# Velvet_Controller.net
KiCad netlist of a schematic drawn in Altium Designer
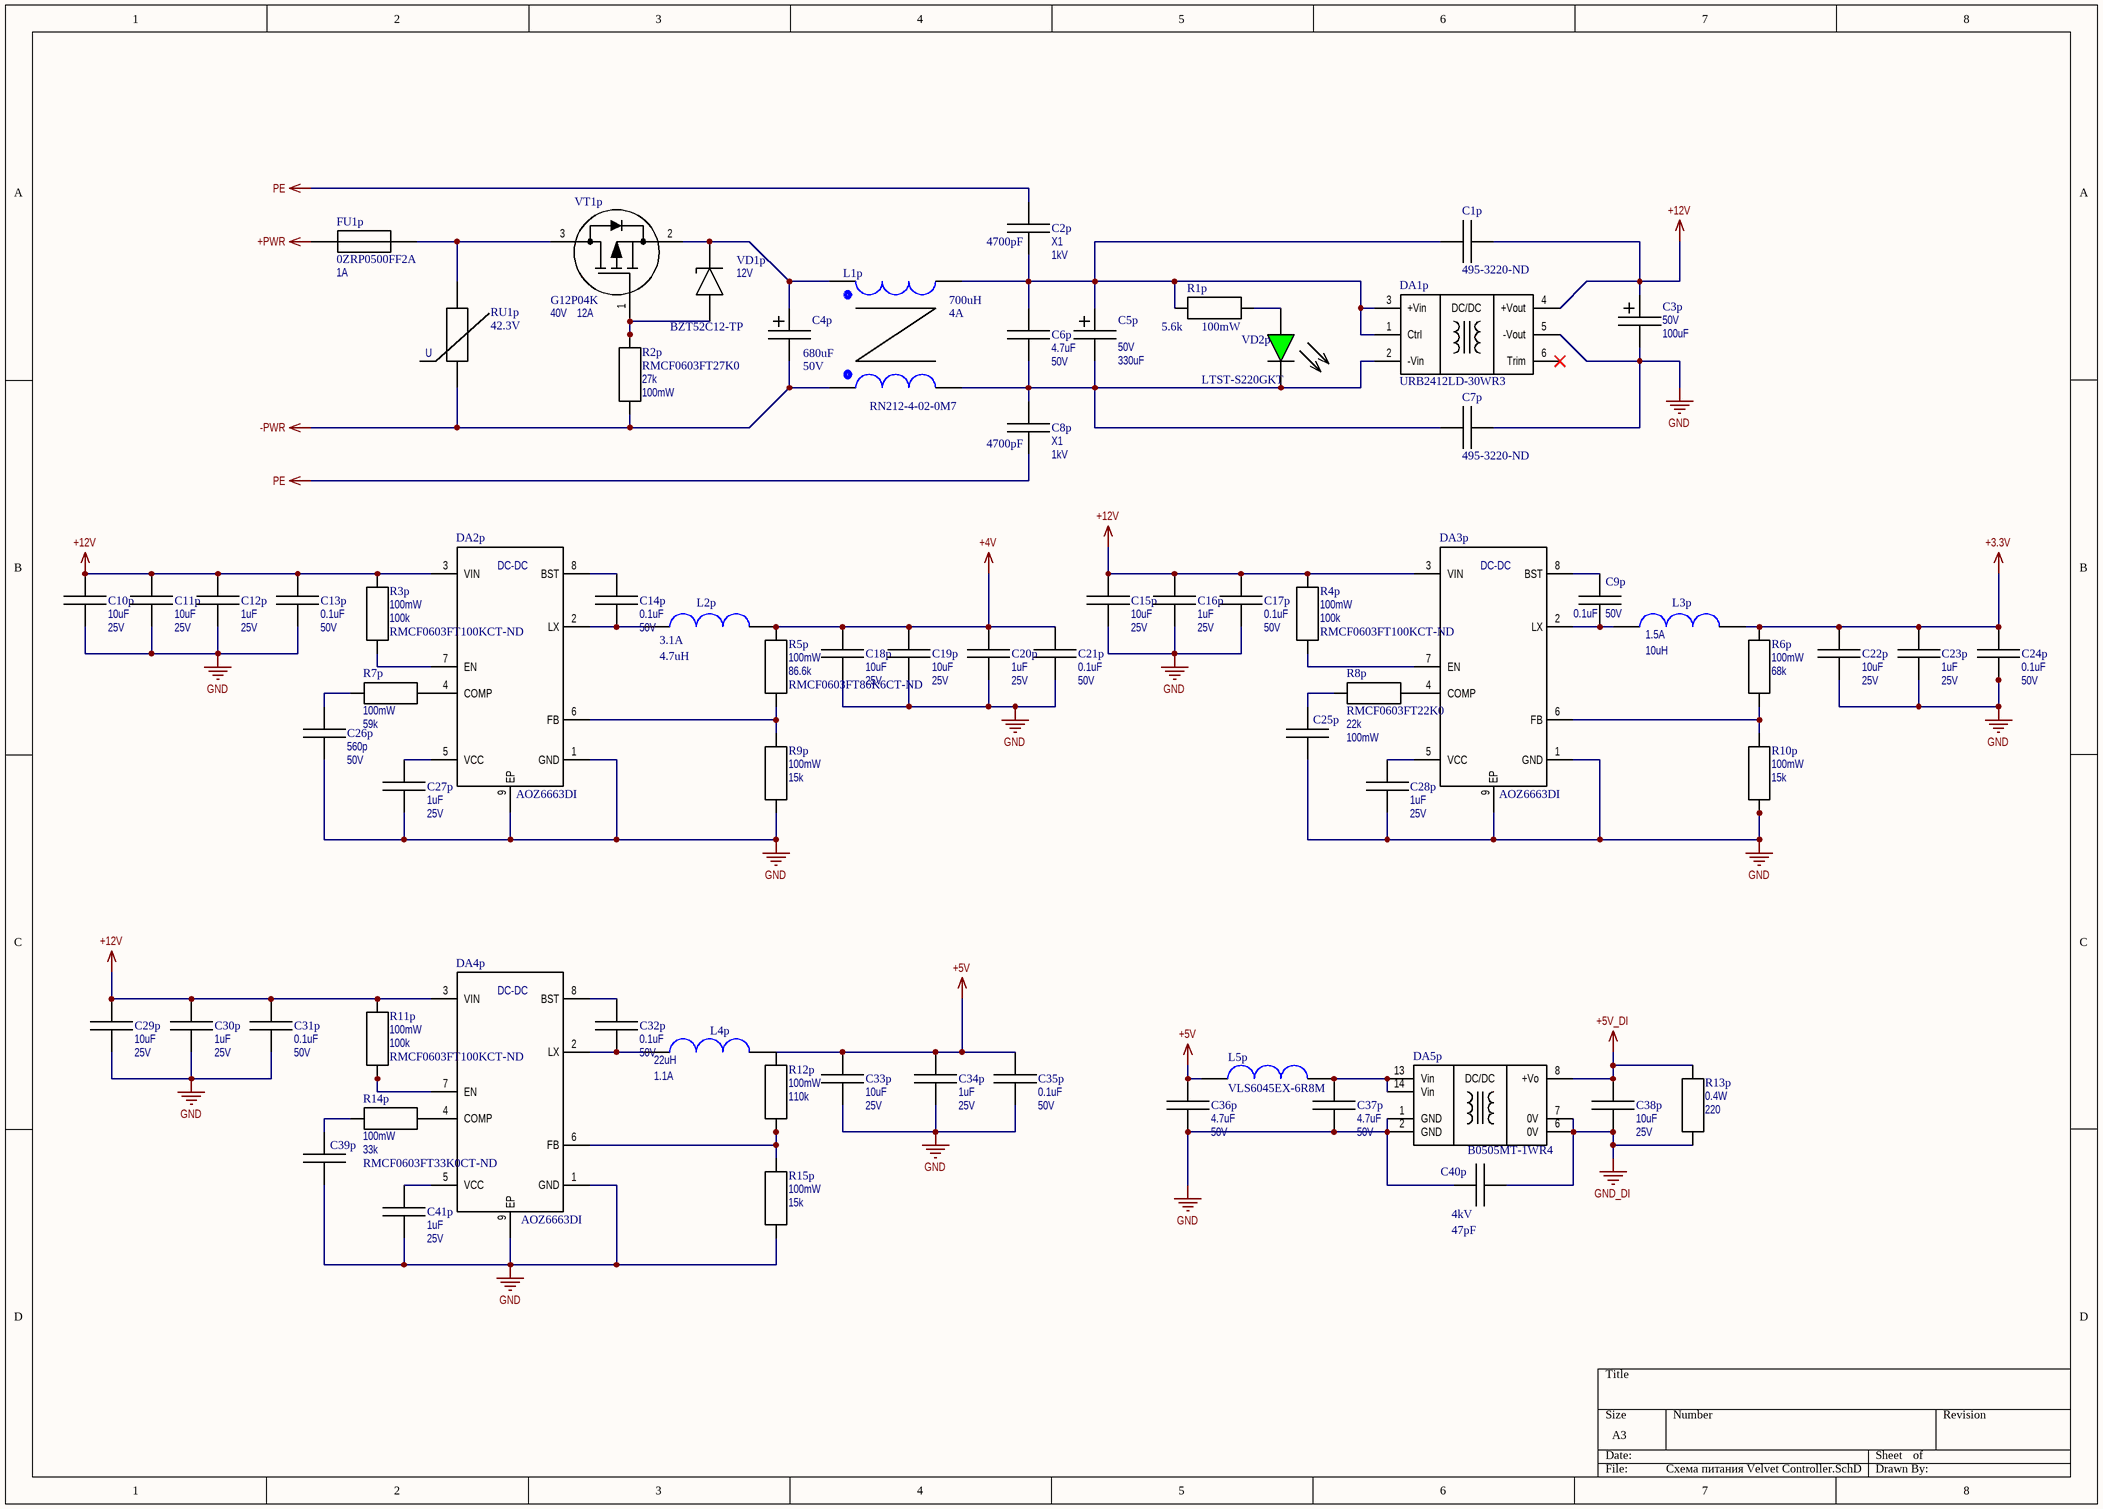
[diagram p0: Схема питания Velvet Controller.SchDoc]

(export (version "E")
  (design (tool "Eeschema 10.0.6"))
  (components
    (comp (ref "C1p")
      (value "B32672L8122J000")
      (footprint "CAP RADIAL L18.0 W5.0 H10.5 P15.0")
      (description "CAP FILM 1200PF 5% 2KVDC RADIAL")
      (fields (field (name "TOLERANCE") "5%") (field (name "SUPPLIER PART NUMBER 1") "495-3220-ND"))
      (libsource (lib "Passive components") (part "B32672L8122J000"))
    )
    (comp (ref "C2p")
      (value "R474F147050A1M")
      (footprint "CAP RADIAL L13.0 W4.0 H9.1 P10.0")
      (description "CAP FILM 4700PF 20% 1KVDC RAD")
      (fields
        (field (name "TOLERANCE") "20%")
        (field (name "CAPACITANCE") "4700pF")
        (field (name "TYPE") "X1")
        (field (name "RATED VOLTAGE") "1kV")
      )
      (libsource (lib "Passive components") (part "R474F147050A1M"))
    )
    (comp (ref "C3p")
      (value "ECA-1HM101B")
      (footprint "CAP RADIAL D8.0 L12.0 P5.0")
      (description "CAP ALUM 100UF 20% 50V RADIAL")
      (fields
        (field (name "TOLERANCE") "20%")
        (field (name "VOLTAGE RATED") "50V")
        (field (name "CAPACITANCE") "100uF")
      )
      (libsource (lib "Passive components") (part "ECA-1HM101B"))
    )
    (comp (ref "C4p")
      (value "50PX680MEFC12.5X20")
      (footprint "CAP RADIAL D12.5 L20.0 P5.0")
      (description "CAP ALUM 680UF 20% 50V RADIAL")
      (fields
        (field (name "CAPACITANCE") "680uF")
        (field (name "VOLTAGE RATED") "50V")
        (field (name "TOLERANCE") "20%")
      )
      (libsource (lib "Passive components") (part "50PX680MEFC12.5X20"))
    )
    (comp (ref "C5p")
      (value "ECA-1HM331B")
      (footprint "CAP RADIAL D10.0 L17,0 P5.0")
      (description "CAP ALUM 330UF 20% 50V RADIAL")
      (fields
        (field (name "TOLERANCE") "20%")
        (field (name "VOLTAGE RATED") "50V")
        (field (name "CAPACITANCE") "330uF")
      )
      (libsource (lib "Passive components") (part "ECA-1HM331B"))
    )
    (comp (ref "C6p")
      (value "CL21A475KBQNNNE")
      (footprint "CAP 0805 IPC MAX")
      (description "CAP SMD CER 4.7UF 50V X5R 0805")
      (fields
        (field (name "TOLERANCE") "10%")
        (field (name "CAPACITANCE") "4.7uF")
        (field (name "RATED VOLTAGE") "50V")
      )
      (libsource (lib "Passive components") (part "CL21A475KBQNNNE"))
    )
    (comp (ref "C7p")
      (value "B32672L8122J000")
      (footprint "CAP RADIAL L18.0 W5.0 H10.5 P15.0")
      (description "CAP FILM 1200PF 5% 2KVDC RADIAL")
      (fields (field (name "TOLERANCE") "5%") (field (name "SUPPLIER PART NUMBER 1") "495-3220-ND"))
      (libsource (lib "Passive components") (part "B32672L8122J000"))
    )
    (comp (ref "C8p")
      (value "R474F147050A1M")
      (footprint "CAP RADIAL L13.0 W4.0 H9.1 P10.0")
      (description "CAP FILM 4700PF 20% 1KVDC RAD")
      (fields
        (field (name "TOLERANCE") "20%")
        (field (name "CAPACITANCE") "4700pF")
        (field (name "TYPE") "X1")
        (field (name "RATED VOLTAGE") "1kV")
      )
      (libsource (lib "Passive components") (part "R474F147050A1M"))
    )
    (comp (ref "C9p")
      (value "GCM188R71H104KA57D")
      (footprint "CAP 0603 IPC MAX")
      (description "CAP SMD CER 0.1UF 50V X7R 0603")
      (fields
        (field (name "TOLERANCE") "10%")
        (field (name "CAPACITANCE") "0.1uF")
        (field (name "RATED VOLTAGE") "50V")
      )
      (libsource (lib "Passive components") (part "GCM188R71H104KA57D"))
    )
    (comp (ref "C10p")
      (value "CL31B106KAHNNNE")
      (footprint "CAP 1206 IPC MAX")
      (description "CAP SMD CER 10UF 25V X7R 1206")
      (fields
        (field (name "TOLERANCE") "10%")
        (field (name "CAPACITANCE") "10uF")
        (field (name "RATED VOLTAGE") "25V")
      )
      (libsource (lib "Passive components") (part "CL31B106KAHNNNE"))
    )
    (comp (ref "C11p")
      (value "CL31B106KAHNNNE")
      (footprint "CAP 1206 IPC MAX")
      (description "CAP SMD CER 10UF 25V X7R 1206")
      (fields
        (field (name "TOLERANCE") "10%")
        (field (name "CAPACITANCE") "10uF")
        (field (name "RATED VOLTAGE") "25V")
      )
      (libsource (lib "Passive components") (part "CL31B106KAHNNNE"))
    )
    (comp (ref "C12p")
      (value "TMK107BJ105KA-T")
      (footprint "CAP 0603 IPC MAX")
      (description "CAP SMD CER 1UF 25V X5R 0603")
      (fields
        (field (name "TOLERANCE") "10%")
        (field (name "CAPACITANCE") "1uF")
        (field (name "RATED VOLTAGE") "25V")
      )
      (libsource (lib "Passive components") (part "TMK107BJ105KA-T"))
    )
    (comp (ref "C13p")
      (value "GCM188R71H104KA57D")
      (footprint "CAP 0603 IPC MAX")
      (description "CAP SMD CER 0.1UF 50V X7R 0603")
      (fields
        (field (name "TOLERANCE") "10%")
        (field (name "CAPACITANCE") "0.1uF")
        (field (name "RATED VOLTAGE") "50V")
      )
      (libsource (lib "Passive components") (part "GCM188R71H104KA57D"))
    )
    (comp (ref "C14p")
      (value "GCM188R71H104KA57D")
      (footprint "CAP 0603 IPC MAX")
      (description "CAP SMD CER 0.1UF 50V X7R 0603")
      (fields
        (field (name "TOLERANCE") "10%")
        (field (name "CAPACITANCE") "0.1uF")
        (field (name "RATED VOLTAGE") "50V")
      )
      (libsource (lib "Passive components") (part "GCM188R71H104KA57D"))
    )
    (comp (ref "C15p")
      (value "CL31B106KAHNNNE")
      (footprint "CAP 1206 IPC MAX")
      (description "CAP SMD CER 10UF 25V X7R 1206")
      (fields
        (field (name "TOLERANCE") "10%")
        (field (name "CAPACITANCE") "10uF")
        (field (name "RATED VOLTAGE") "25V")
      )
      (libsource (lib "Passive components") (part "CL31B106KAHNNNE"))
    )
    (comp (ref "C16p")
      (value "TMK107BJ105KA-T")
      (footprint "CAP 0603 IPC MAX")
      (description "CAP SMD CER 1UF 25V X5R 0603")
      (fields
        (field (name "TOLERANCE") "10%")
        (field (name "CAPACITANCE") "1uF")
        (field (name "RATED VOLTAGE") "25V")
      )
      (libsource (lib "Passive components") (part "TMK107BJ105KA-T"))
    )
    (comp (ref "C17p")
      (value "GCM188R71H104KA57D")
      (footprint "CAP 0603 IPC MAX")
      (description "CAP SMD CER 0.1UF 50V X7R 0603")
      (fields
        (field (name "TOLERANCE") "10%")
        (field (name "CAPACITANCE") "0.1uF")
        (field (name "RATED VOLTAGE") "50V")
      )
      (libsource (lib "Passive components") (part "GCM188R71H104KA57D"))
    )
    (comp (ref "C18p")
      (value "CL31B106KAHNNNE")
      (footprint "CAP 1206 IPC MAX")
      (description "CAP SMD CER 10UF 25V X7R 1206")
      (fields
        (field (name "TOLERANCE") "10%")
        (field (name "CAPACITANCE") "10uF")
        (field (name "RATED VOLTAGE") "25V")
      )
      (libsource (lib "Passive components") (part "CL31B106KAHNNNE"))
    )
    (comp (ref "C19p")
      (value "CL31B106KAHNNNE")
      (footprint "CAP 1206 IPC MAX")
      (description "CAP SMD CER 10UF 25V X7R 1206")
      (fields
        (field (name "TOLERANCE") "10%")
        (field (name "CAPACITANCE") "10uF")
        (field (name "RATED VOLTAGE") "25V")
      )
      (libsource (lib "Passive components") (part "CL31B106KAHNNNE"))
    )
    (comp (ref "C20p")
      (value "TMK107BJ105KA-T")
      (footprint "CAP 0603 IPC MAX")
      (description "CAP SMD CER 1UF 25V X5R 0603")
      (fields
        (field (name "TOLERANCE") "10%")
        (field (name "CAPACITANCE") "1uF")
        (field (name "RATED VOLTAGE") "25V")
      )
      (libsource (lib "Passive components") (part "TMK107BJ105KA-T"))
    )
    (comp (ref "C21p")
      (value "GCM188R71H104KA57D")
      (footprint "CAP 0603 IPC MAX")
      (description "CAP SMD CER 0.1UF 50V X7R 0603")
      (fields
        (field (name "TOLERANCE") "10%")
        (field (name "CAPACITANCE") "0.1uF")
        (field (name "RATED VOLTAGE") "50V")
      )
      (libsource (lib "Passive components") (part "GCM188R71H104KA57D"))
    )
    (comp (ref "C22p")
      (value "CL31B106KAHNNNE")
      (footprint "CAP 1206 IPC MAX")
      (description "CAP SMD CER 10UF 25V X7R 1206")
      (fields
        (field (name "TOLERANCE") "10%")
        (field (name "CAPACITANCE") "10uF")
        (field (name "RATED VOLTAGE") "25V")
      )
      (libsource (lib "Passive components") (part "CL31B106KAHNNNE"))
    )
    (comp (ref "C23p")
      (value "TMK107BJ105KA-T")
      (footprint "CAP 0603 IPC MAX")
      (description "CAP SMD CER 1UF 25V X5R 0603")
      (fields
        (field (name "TOLERANCE") "10%")
        (field (name "CAPACITANCE") "1uF")
        (field (name "RATED VOLTAGE") "25V")
      )
      (libsource (lib "Passive components") (part "TMK107BJ105KA-T"))
    )
    (comp (ref "C24p")
      (value "GCM188R71H104KA57D")
      (footprint "CAP 0603 IPC MAX")
      (description "CAP SMD CER 0.1UF 50V X7R 0603")
      (fields
        (field (name "TOLERANCE") "10%")
        (field (name "CAPACITANCE") "0.1uF")
        (field (name "RATED VOLTAGE") "50V")
      )
      (libsource (lib "Passive components") (part "GCM188R71H104KA57D"))
    )
    (comp (ref "C25p")
      (value "CAP")
      (footprint "RES 0603 IPC MAX")
      (description "CAP ??UF ??% ??V Package?")
      (libsource (lib "Passive components") (part "CAP GOST"))
    )
    (comp (ref "C26p")
      (value "CC0603KRX7R9BB561")
      (footprint "CAP 0603 IPC MAX")
      (description "CAP SMD CER 560PF 50V X7R 0603")
      (fields
        (field (name "TOLERANCE") "10%")
        (field (name "CAPACITANCE") "560p")
        (field (name "RATED VOLTAGE") "50V")
      )
      (libsource (lib "Passive components") (part "CC0603KRX7R9BB561"))
    )
    (comp (ref "C27p")
      (value "TMK107BJ105KA-T")
      (footprint "CAP 0603 IPC MAX")
      (description "CAP SMD CER 1UF 25V X5R 0603")
      (fields
        (field (name "TOLERANCE") "10%")
        (field (name "CAPACITANCE") "1uF")
        (field (name "RATED VOLTAGE") "25V")
      )
      (libsource (lib "Passive components") (part "TMK107BJ105KA-T"))
    )
    (comp (ref "C28p")
      (value "TMK107BJ105KA-T")
      (footprint "CAP 0603 IPC MAX")
      (description "CAP SMD CER 1UF 25V X5R 0603")
      (fields
        (field (name "TOLERANCE") "10%")
        (field (name "CAPACITANCE") "1uF")
        (field (name "RATED VOLTAGE") "25V")
      )
      (libsource (lib "Passive components") (part "TMK107BJ105KA-T"))
    )
    (comp (ref "C29p")
      (value "CL31B106KAHNNNE")
      (footprint "CAP 1206 IPC MAX")
      (description "CAP SMD CER 10UF 25V X7R 1206")
      (fields
        (field (name "TOLERANCE") "10%")
        (field (name "CAPACITANCE") "10uF")
        (field (name "RATED VOLTAGE") "25V")
      )
      (libsource (lib "Passive components") (part "CL31B106KAHNNNE"))
    )
    (comp (ref "C30p")
      (value "TMK107BJ105KA-T")
      (footprint "CAP 0603 IPC MAX")
      (description "CAP SMD CER 1UF 25V X5R 0603")
      (fields
        (field (name "TOLERANCE") "10%")
        (field (name "CAPACITANCE") "1uF")
        (field (name "RATED VOLTAGE") "25V")
      )
      (libsource (lib "Passive components") (part "TMK107BJ105KA-T"))
    )
    (comp (ref "C31p")
      (value "GCM188R71H104KA57D")
      (footprint "CAP 0603 IPC MAX")
      (description "CAP SMD CER 0.1UF 50V X7R 0603")
      (fields
        (field (name "TOLERANCE") "10%")
        (field (name "CAPACITANCE") "0.1uF")
        (field (name "RATED VOLTAGE") "50V")
      )
      (libsource (lib "Passive components") (part "GCM188R71H104KA57D"))
    )
    (comp (ref "C32p")
      (value "GCM188R71H104KA57D")
      (footprint "CAP 0603 IPC MAX")
      (description "CAP SMD CER 0.1UF 50V X7R 0603")
      (fields
        (field (name "TOLERANCE") "10%")
        (field (name "CAPACITANCE") "0.1uF")
        (field (name "RATED VOLTAGE") "50V")
      )
      (libsource (lib "Passive components") (part "GCM188R71H104KA57D"))
    )
    (comp (ref "C33p")
      (value "CL31B106KAHNNNE")
      (footprint "CAP 1206 IPC MAX")
      (description "CAP SMD CER 10UF 25V X7R 1206")
      (fields
        (field (name "TOLERANCE") "10%")
        (field (name "CAPACITANCE") "10uF")
        (field (name "RATED VOLTAGE") "25V")
      )
      (libsource (lib "Passive components") (part "CL31B106KAHNNNE"))
    )
    (comp (ref "C34p")
      (value "TMK107BJ105KA-T")
      (footprint "CAP 0603 IPC MAX")
      (description "CAP SMD CER 1UF 25V X5R 0603")
      (fields
        (field (name "TOLERANCE") "10%")
        (field (name "CAPACITANCE") "1uF")
        (field (name "RATED VOLTAGE") "25V")
      )
      (libsource (lib "Passive components") (part "TMK107BJ105KA-T"))
    )
    (comp (ref "C35p")
      (value "GCM188R71H104KA57D")
      (footprint "CAP 0603 IPC MAX")
      (description "CAP SMD CER 0.1UF 50V X7R 0603")
      (fields
        (field (name "TOLERANCE") "10%")
        (field (name "CAPACITANCE") "0.1uF")
        (field (name "RATED VOLTAGE") "50V")
      )
      (libsource (lib "Passive components") (part "GCM188R71H104KA57D"))
    )
    (comp (ref "C36p")
      (value "CL21A475KBQNNNE")
      (footprint "CAP 0805 IPC MAX")
      (description "CAP SMD CER 4.7UF 50V X5R 0805")
      (fields
        (field (name "TOLERANCE") "10%")
        (field (name "CAPACITANCE") "4.7uF")
        (field (name "RATED VOLTAGE") "50V")
      )
      (libsource (lib "Passive components") (part "CL21A475KBQNNNE"))
    )
    (comp (ref "C37p")
      (value "CL21A475KBQNNNE")
      (footprint "CAP 0805 IPC MAX")
      (description "CAP SMD CER 4.7UF 50V X5R 0805")
      (fields
        (field (name "TOLERANCE") "10%")
        (field (name "CAPACITANCE") "4.7uF")
        (field (name "RATED VOLTAGE") "50V")
      )
      (libsource (lib "Passive components") (part "CL21A475KBQNNNE"))
    )
    (comp (ref "C38p")
      (value "CL31B106KAHNNNE")
      (footprint "CAP 1206 IPC MAX")
      (description "CAP SMD CER 10UF 25V X7R 1206")
      (fields
        (field (name "TOLERANCE") "10%")
        (field (name "CAPACITANCE") "10uF")
        (field (name "RATED VOLTAGE") "25V")
      )
      (libsource (lib "Passive components") (part "CL31B106KAHNNNE"))
    )
    (comp (ref "C39p")
      (value "CAP")
      (footprint "RES 0603 IPC MAX")
      (description "CAP ??UF ??% ??V Package?")
      (libsource (lib "Passive components") (part "CAP GOST"))
    )
    (comp (ref "C40p")
      (value "CC45SL3JD470JYVNA")
      (footprint "CC45SL3JD470JYVNA")
      (description "CAP SMD CER 47PF 6KV SL RADIAL")
      (fields
        (field (name "CAPACITANCE") "47pF")
        (field (name "TOLERANCE") "5%")
        (field (name "RATED VOLTAGE") "4kV")
      )
      (libsource (lib "Passive components") (part "CC45SL3JD470JYVNA"))
    )
    (comp (ref "C41p")
      (value "TMK107BJ105KA-T")
      (footprint "CAP 0603 IPC MAX")
      (description "CAP SMD CER 1UF 25V X5R 0603")
      (fields
        (field (name "TOLERANCE") "10%")
        (field (name "CAPACITANCE") "1uF")
        (field (name "RATED VOLTAGE") "25V")
      )
      (libsource (lib "Passive components") (part "TMK107BJ105KA-T"))
    )
    (comp (ref "DA1p")
      (value "URB2412LD-30WR3")
      (footprint "URB2412LD-30WR3")
      (description "DC DC CONVERTER 12V 30W")
      (libsource (lib "Power") (part "URB2412LD-30WR3"))
    )
    (comp (ref "DA2p")
      (value "AOZ6663DI")
      (footprint "DFN 3x3-8L")
      (description "IC REG BUCK ADJ 3A 8DFN")
      (libsource (lib "Power") (part "AOZ6663DI"))
    )
    (comp (ref "DA3p")
      (value "AOZ6663DI")
      (footprint "DFN 3x3-8L")
      (description "IC REG BUCK ADJ 3A 8DFN")
      (libsource (lib "Power") (part "AOZ6663DI"))
    )
    (comp (ref "DA4p")
      (value "AOZ6663DI")
      (footprint "DFN 3x3-8L")
      (description "IC REG BUCK ADJ 3A 8DFN")
      (libsource (lib "Power") (part "AOZ6663DI"))
    )
    (comp (ref "DA5p")
      (value "B0505MT-1WR4")
      (footprint "B0505MT-1WR4")
      (description "DC DC CONVERTER 5V 1W")
      (libsource (lib "Power") (part "B0505MT-1WR4"))
    )
    (comp (ref "FU1p")
      (value "0ZRP0500FF2A")
      (footprint "0ZRP0500FF2A")
      (description "PTC RESET FUSE 60V 5A RADIAL")
      (fields (field (name "CURRENT HOLD") "1A"))
      (libsource (lib "Power") (part "0ZRP0500FF2A"))
    )
    (comp (ref "L1p")
      (value "RN212-4-02-0M7")
      (footprint "FIXED IND RN212-4-02-0M7")
      (description "COMMON MODE CHOKE 700UH 4A 2LN TH")
      (fields (field (name "INDUCTANCE") "700uH") (field (name "CURRENT RATING") "4A"))
      (libsource (lib "Passive components") (part "RN212-4-02-0M7"))
    )
    (comp (ref "L2p")
      (value "SRN5040-4R7M")
      (footprint "SRN5040")
      (description "FIXED IND 4.7UH 3.1A 35 MOHM SMD")
      (fields (field (name "INDUCTANCE") "4.7uH") (field (name "CURRENT RATING") "3.1A"))
      (libsource (lib "Passive components") (part "SRN5040-4R7M"))
    )
    (comp (ref "L3p")
      (value "ASPI-4030S-100M-T")
      (footprint "ASPI-4030S")
      (description "FIXED IND 10UH 1.5A 100 MOHM SMD")
      (fields (field (name "INDUCTANCE") "10uH") (field (name "CURRENT RATING") "1.5A"))
      (libsource (lib "Passive components") (part "ASPI-4030S-100M-T"))
    )
    (comp (ref "L4p")
      (value "TYS5020220M-10")
      (footprint "TYS5020")
      (description "FIXED IND 22UH 1.1A 226 MOHM SMD")
      (fields (field (name "INDUCTANCE") "22uH") (field (name "CURRENT RATING") "1.1A"))
      (libsource (lib "Passive components") (part "TYS5020220M-10"))
    )
    (comp (ref "L5p")
      (value "VLS6045EX-6R8M")
      (footprint "VLS6045EX")
      (description "FIXED IND 6.8UH 3.6A 36 MOHM SMD")
      (libsource (lib "Passive components") (part "VLS6045EX-6R8M"))
    )
    (comp (ref "R1p")
      (value "RMCF0603FT5K60")
      (footprint "RES 0603 IPC MAX")
      (description "RES SMD 5.6K OHM 1% 1/10W 0603")
      (fields
        (field (name "RESISTANCE") "5.6k")
        (field (name "TOLERANCE") "1%")
        (field (name "RATED POWER") "100mW")
      )
      (libsource (lib "Passive components") (part "RMCF0603FT5K60"))
    )
    (comp (ref "R2p")
      (value "RMCF0603FT27K0")
      (footprint "RES 0603 IPC MAX")
      (description "RES SMD 27K OHM 1% 1/10W 0603")
      (fields
        (field (name "TOLERANCE") "1%")
        (field (name "RESISTANCE") "27k")
        (field (name "RATED POWER") "100mW")
      )
      (libsource (lib "Passive components") (part "RMCF0603FT27K0"))
    )
    (comp (ref "R3p")
      (value "RMCF0603FT100K")
      (footprint "RES 0603 IPC MAX")
      (description "RES SMD 100K OHM 5% 1/10W 0603")
      (fields
        (field (name "TOLERANCE") "5%")
        (field (name "POWER RATED") "100mW")
        (field (name "RESISTANCE") "100k")
        (field (name "SUPPLIER PART NUMBER 1") "RMCF0603FT100KCT-ND")
      )
      (libsource (lib "Passive components") (part "RMCF0603FT100K"))
    )
    (comp (ref "R4p")
      (value "RMCF0603FT100K")
      (footprint "RES 0603 IPC MAX")
      (description "RES SMD 100K OHM 5% 1/10W 0603")
      (fields
        (field (name "TOLERANCE") "5%")
        (field (name "POWER RATED") "100mW")
        (field (name "RESISTANCE") "100k")
        (field (name "SUPPLIER PART NUMBER 1") "RMCF0603FT100KCT-ND")
      )
      (libsource (lib "Passive components") (part "RMCF0603FT100K"))
    )
    (comp (ref "R5p")
      (value "RMCF0603FT86K6")
      (footprint "RES 0603 IPC MAX")
      (description "RES SMD 86.6K OHM 5% 1/10W 0603")
      (fields
        (field (name "TOLERANCE") "5%")
        (field (name "POWER RATED") "100mW")
        (field (name "RESISTANCE") "86.6k")
        (field (name "SUPPLIER PART NUMBER 1") "RMCF0603FT86K6CT-ND")
      )
      (libsource (lib "Passive components") (part "RMCF0603FT86K6"))
    )
    (comp (ref "R6p")
      (value "RMCF0603FT68K0")
      (footprint "RES 0603 IPC MAX")
      (description "RES SMD 68K OHM 1% 1/10W 0603")
      (fields
        (field (name "TOLERANCE") "1%")
        (field (name "POWER RATED") "100mW")
        (field (name "RESISTANCE") "68k")
      )
      (libsource (lib "Passive components") (part "RMCF0603FT68K0"))
    )
    (comp (ref "R7p")
      (value "RMCF0603FT59K0")
      (footprint "RES 0603 IPC MAX")
      (description "RES SMD 59K OHM 5% 1/10W 0603")
      (fields
        (field (name "TOLERANCE") "5%")
        (field (name "POWER RATED") "100mW")
        (field (name "RESISTANCE") "59k")
      )
      (libsource (lib "Passive components") (part "RMCF0603FT59K0"))
    )
    (comp (ref "R8p")
      (value "RMCF0603FT22K0")
      (footprint "RES 0603 IPC MAX")
      (description "RES SMD 22K OHM 1% 1/10W 0603")
      (fields
        (field (name "TOLERANCE") "1%")
        (field (name "RESISTANCE") "22k")
        (field (name "POWER RATED") "100mW")
      )
      (libsource (lib "Passive components") (part "RMCF0603FT22K0"))
    )
    (comp (ref "R9p")
      (value "RMCF0603FT15K0")
      (footprint "RES 0603 IPC MAX")
      (description "RES SMD 15K OHM 1% 1/10W 0603")
      (fields
        (field (name "TOLERANCE") "1%")
        (field (name "POWER RATED") "100mW")
        (field (name "RESISTANCE") "15k")
      )
      (libsource (lib "Passive components") (part "RMCF0603FT15K0"))
    )
    (comp (ref "R10p")
      (value "RMCF0603FT15K0")
      (footprint "RES 0603 IPC MAX")
      (description "RES SMD 15K OHM 1% 1/10W 0603")
      (fields
        (field (name "TOLERANCE") "1%")
        (field (name "POWER RATED") "100mW")
        (field (name "RESISTANCE") "15k")
      )
      (libsource (lib "Passive components") (part "RMCF0603FT15K0"))
    )
    (comp (ref "R11p")
      (value "RMCF0603FT100K")
      (footprint "RES 0603 IPC MAX")
      (description "RES SMD 100K OHM 5% 1/10W 0603")
      (fields
        (field (name "TOLERANCE") "5%")
        (field (name "POWER RATED") "100mW")
        (field (name "RESISTANCE") "100k")
        (field (name "SUPPLIER PART NUMBER 1") "RMCF0603FT100KCT-ND")
      )
      (libsource (lib "Passive components") (part "RMCF0603FT100K"))
    )
    (comp (ref "R12p")
      (value "RMCF0603FT110K")
      (footprint "RES 0603 IPC MAX")
      (description "RES SMD 110K OHM 1% 1/10W 0603")
      (fields
        (field (name "TOLERANCE") "5%")
        (field (name "POWER RATED") "100mW")
        (field (name "RESISTANCE") "110k")
      )
      (libsource (lib "Passive components") (part "RMCF0603FT110K"))
    )
    (comp (ref "R13p")
      (value "ESR10EZPF2200")
      (footprint "RES 0805 IPC MAX")
      (description "RES SMD 220 OHM 1% 0.4W 0805")
      (fields
        (field (name "TOLERANCE") "1%")
        (field (name "POWER RATED") "0.4W")
        (field (name "RESISTANCE") "220")
      )
      (libsource (lib "Passive components") (part "ESR10EZPF2200"))
    )
    (comp (ref "R14p")
      (value "RMCF0603FT33K0")
      (footprint "RES 0603 IPC MAX")
      (description "RES SMD 33K OHM 1% 1/10W 0603")
      (fields
        (field (name "TOLERANCE") "1%")
        (field (name "POWER RATED") "100mW")
        (field (name "RESISTANCE") "33k")
        (field (name "SUPPLIER PART NUMBER 1") "RMCF0603FT33K0CT-ND")
      )
      (libsource (lib "Passive components") (part "RMCF0603FT33K0"))
    )
    (comp (ref "R15p")
      (value "RMCF0603FT15K0")
      (footprint "RES 0603 IPC MAX")
      (description "RES SMD 15K OHM 1% 1/10W 0603")
      (fields
        (field (name "TOLERANCE") "1%")
        (field (name "POWER RATED") "100mW")
        (field (name "RESISTANCE") "15k")
      )
      (libsource (lib "Passive components") (part "RMCF0603FT15K0"))
    )
    (comp (ref "RU1p")
      (value "B72220S0300K101")
      (footprint "B72220S0300K101")
      (description "VARISTOR 47V 2KA DISC 20MM S20K30")
      (fields (field (name "MANUFACTURER") "EPCOS Inc") (field (name "VARISTOR VOLTAGE (MIN)") "42.3V"))
      (libsource (lib "Power") (part "B72220S0300K101"))
    )
    (comp (ref "VD1p")
      (value "BZT52C12-TP")
      (footprint "SOD-123 (Marked)")
      (description "DIODE ZENER 12V 200MW SOD123")
      (fields (field (name "TOLERANCE") "5%") (field (name "ZENER VOLTAGE") "12V"))
      (libsource (lib "Diodes") (part "BZT52C12-TP"))
    )
    (comp (ref "VD2p")
      (value "LTST-S220GKT")
      (footprint "0805 DIODE")
      (description "LED GREEN CLEAR SMD R/A")
      (libsource (lib "Diodes") (part "LTST-S220GKT"))
    )
    (comp (ref "VT1p")
      (value "G12P04K")
      (footprint "TO-252 (D-PAK)")
      (description "MOSFET P-CH 40V 12A TO-252")
      (fields (field (name "VDS MAX") "40V") (field (name "MAX DRAIN CURRENT") "12A"))
      (libsource (lib "MOSFET") (part "G12P04K"))
    )
  )
  (nets
    (net (code "1") (name "+3.3V") (class "Default")
      (node (ref "C22p") (pin "1") (pinfunction "1_1") (pintype "passive"))
      (node (ref "C23p") (pin "1") (pinfunction "1_1") (pintype "passive"))
      (node (ref "C24p") (pin "1") (pinfunction "1_1") (pintype "passive"))
      (node (ref "L3p") (pin "2") (pinfunction "2_2") (pintype "passive"))
      (node (ref "R6p") (pin "1") (pinfunction "1_1") (pintype "passive"))
    )
    (net (code "2") (name "+4V") (class "Default")
      (node (ref "C18p") (pin "1") (pinfunction "1_1") (pintype "passive"))
      (node (ref "C19p") (pin "1") (pinfunction "1_1") (pintype "passive"))
      (node (ref "C20p") (pin "1") (pinfunction "1_1") (pintype "passive"))
      (node (ref "C21p") (pin "1") (pinfunction "1_1") (pintype "passive"))
      (node (ref "L2p") (pin "2") (pinfunction "2_2") (pintype "passive"))
      (node (ref "R5p") (pin "1") (pinfunction "1_1") (pintype "passive"))
    )
    (net (code "3") (name "+5V") (class "Default")
      (node (ref "C33p") (pin "1") (pinfunction "1_1") (pintype "passive"))
      (node (ref "C34p") (pin "1") (pinfunction "1_1") (pintype "passive"))
      (node (ref "C35p") (pin "1") (pinfunction "1_1") (pintype "passive"))
      (node (ref "C36p") (pin "1") (pinfunction "1_1") (pintype "passive"))
      (node (ref "L4p") (pin "2") (pinfunction "2_2") (pintype "passive"))
      (node (ref "L5p") (pin "1") (pinfunction "1_1") (pintype "passive"))
      (node (ref "R12p") (pin "2") (pinfunction "2_2") (pintype "passive"))
    )
    (net (code "4") (name "+5V_DI") (class "Default")
      (node (ref "C38p") (pin "1") (pinfunction "1_1") (pintype "passive"))
      (node (ref "DA5p") (pin "8") (pinfunction "+Vo_8") (pintype "passive"))
      (node (ref "R13p") (pin "2") (pinfunction "2_2") (pintype "passive"))
    )
    (net (code "5") (name "+12V") (class "Default")
      (node (ref "C10p") (pin "1") (pinfunction "1_1") (pintype "passive"))
      (node (ref "C11p") (pin "1") (pinfunction "1_1") (pintype "passive"))
      (node (ref "C12p") (pin "1") (pinfunction "1_1") (pintype "passive"))
      (node (ref "C13p") (pin "1") (pinfunction "1_1") (pintype "passive"))
      (node (ref "C15p") (pin "1") (pinfunction "1_1") (pintype "passive"))
      (node (ref "C16p") (pin "1") (pinfunction "1_1") (pintype "passive"))
      (node (ref "C17p") (pin "1") (pinfunction "1_1") (pintype "passive"))
      (node (ref "C1p") (pin "2") (pinfunction "2_2") (pintype "passive"))
      (node (ref "C29p") (pin "1") (pinfunction "1_1") (pintype "passive"))
      (node (ref "C30p") (pin "1") (pinfunction "1_1") (pintype "passive"))
      (node (ref "C31p") (pin "1") (pinfunction "1_1") (pintype "passive"))
      (node (ref "C3p") (pin "1") (pinfunction "1_1") (pintype "passive"))
      (node (ref "DA1p") (pin "4") (pinfunction "+Vout_4") (pintype "passive"))
      (node (ref "DA2p") (pin "3") (pinfunction "VIN_3") (pintype "passive"))
      (node (ref "DA3p") (pin "3") (pinfunction "VIN_3") (pintype "passive"))
      (node (ref "DA4p") (pin "3") (pinfunction "VIN_3") (pintype "passive"))
      (node (ref "R11p") (pin "1") (pinfunction "1_1") (pintype "passive"))
      (node (ref "R3p") (pin "2") (pinfunction "2_2") (pintype "passive"))
      (node (ref "R4p") (pin "1") (pinfunction "1_1") (pintype "passive"))
    )
    (net (code "6") (name "+PWR") (class "Default")
      (node (ref "FU1p") (pin "1") (pinfunction "1_1") (pintype "passive"))
    )
    (net (code "7") (name "-PWR") (class "Default")
      (node (ref "C4p") (pin "2") (pinfunction "2_2") (pintype "passive"))
      (node (ref "L1p") (pin "3") (pinfunction "3_3") (pintype "passive"))
      (node (ref "R2p") (pin "1") (pinfunction "1_1") (pintype "passive"))
      (node (ref "RU1p") (pin "1") (pinfunction "1_1") (pintype "passive"))
    )
    (net (code "8") (name "GND") (class "Default")
      (node (ref "C10p") (pin "2") (pinfunction "2_2") (pintype "passive"))
      (node (ref "C11p") (pin "2") (pinfunction "2_2") (pintype "passive"))
      (node (ref "C12p") (pin "2") (pinfunction "2_2") (pintype "passive"))
      (node (ref "C13p") (pin "2") (pinfunction "2_2") (pintype "passive"))
      (node (ref "C15p") (pin "2") (pinfunction "2_2") (pintype "passive"))
      (node (ref "C16p") (pin "2") (pinfunction "2_2") (pintype "passive"))
      (node (ref "C17p") (pin "2") (pinfunction "2_2") (pintype "passive"))
      (node (ref "C18p") (pin "2") (pinfunction "2_2") (pintype "passive"))
      (node (ref "C19p") (pin "2") (pinfunction "2_2") (pintype "passive"))
      (node (ref "C20p") (pin "2") (pinfunction "2_2") (pintype "passive"))
      (node (ref "C21p") (pin "2") (pinfunction "2_2") (pintype "passive"))
      (node (ref "C22p") (pin "2") (pinfunction "2_2") (pintype "passive"))
      (node (ref "C23p") (pin "2") (pinfunction "2_2") (pintype "passive"))
      (node (ref "C24p") (pin "2") (pinfunction "2_2") (pintype "passive"))
      (node (ref "C25p") (pin "2") (pinfunction "2_2") (pintype "passive"))
      (node (ref "C26p") (pin "2") (pinfunction "2_2") (pintype "passive"))
      (node (ref "C27p") (pin "2") (pinfunction "2_2") (pintype "passive"))
      (node (ref "C28p") (pin "2") (pinfunction "2_2") (pintype "passive"))
      (node (ref "C29p") (pin "2") (pinfunction "2_2") (pintype "passive"))
      (node (ref "C30p") (pin "2") (pinfunction "2_2") (pintype "passive"))
      (node (ref "C31p") (pin "2") (pinfunction "2_2") (pintype "passive"))
      (node (ref "C33p") (pin "2") (pinfunction "2_2") (pintype "passive"))
      (node (ref "C34p") (pin "2") (pinfunction "2_2") (pintype "passive"))
      (node (ref "C35p") (pin "2") (pinfunction "2_2") (pintype "passive"))
      (node (ref "C36p") (pin "2") (pinfunction "2_2") (pintype "passive"))
      (node (ref "C37p") (pin "2") (pinfunction "2_2") (pintype "passive"))
      (node (ref "C39p") (pin "2") (pinfunction "2_2") (pintype "passive"))
      (node (ref "C3p") (pin "2") (pinfunction "2_2") (pintype "passive"))
      (node (ref "C40p") (pin "1") (pinfunction "1_1") (pintype "passive"))
      (node (ref "C41p") (pin "2") (pinfunction "2_2") (pintype "passive"))
      (node (ref "C7p") (pin "2") (pinfunction "2_2") (pintype "passive"))
      (node (ref "DA1p") (pin "5") (pinfunction "-Vout_5") (pintype "passive"))
      (node (ref "DA2p") (pin "1") (pinfunction "GND_1") (pintype "passive"))
      (node (ref "DA2p") (pin "9") (pinfunction "EP_9") (pintype "passive"))
      (node (ref "DA3p") (pin "1") (pinfunction "GND_1") (pintype "passive"))
      (node (ref "DA3p") (pin "9") (pinfunction "EP_9") (pintype "passive"))
      (node (ref "DA4p") (pin "1") (pinfunction "GND_1") (pintype "passive"))
      (node (ref "DA4p") (pin "9") (pinfunction "EP_9") (pintype "passive"))
      (node (ref "DA5p") (pin "1") (pinfunction "GND_1") (pintype "passive"))
      (node (ref "DA5p") (pin "2") (pinfunction "GND_2") (pintype "passive"))
      (node (ref "R10p") (pin "1") (pinfunction "1_1") (pintype "passive"))
      (node (ref "R15p") (pin "1") (pinfunction "1_1") (pintype "passive"))
      (node (ref "R9p") (pin "1") (pinfunction "1_1") (pintype "passive"))
    )
    (net (code "9") (name "GND_DI") (class "Default")
      (node (ref "C38p") (pin "2") (pinfunction "2_2") (pintype "passive"))
      (node (ref "C40p") (pin "2") (pinfunction "2_2") (pintype "passive"))
      (node (ref "DA5p") (pin "6") (pinfunction "0V_6") (pintype "passive"))
      (node (ref "DA5p") (pin "7") (pinfunction "0V_7") (pintype "passive"))
      (node (ref "R13p") (pin "1") (pinfunction "1_1") (pintype "passive"))
    )
    (net (code "10") (name "Net-(C25p-Pad1)") (class "Default")
      (node (ref "C25p") (pin "1") (pinfunction "1_1") (pintype "passive"))
      (node (ref "R8p") (pin "1") (pinfunction "1_1") (pintype "passive"))
    )
    (net (code "11") (name "Net-(C26p-Pad1)") (class "Default")
      (node (ref "C26p") (pin "1") (pinfunction "1_1") (pintype "passive"))
      (node (ref "R7p") (pin "1") (pinfunction "1_1") (pintype "passive"))
    )
    (net (code "12") (name "Net-(C37p-Pad1)") (class "Default")
      (node (ref "C37p") (pin "1") (pinfunction "1_1") (pintype "passive"))
      (node (ref "DA5p") (pin "13") (pinfunction "Vin_13") (pintype "passive"))
      (node (ref "DA5p") (pin "14") (pinfunction "Vin_14") (pintype "passive"))
      (node (ref "L5p") (pin "2") (pinfunction "2_2") (pintype "passive"))
    )
    (net (code "13") (name "Net-(C39p-Pad1)") (class "Default")
      (node (ref "C39p") (pin "1") (pinfunction "1_1") (pintype "passive"))
      (node (ref "R14p") (pin "2") (pinfunction "2_2") (pintype "passive"))
    )
    (net (code "14") (name "Net-(DA1p-+Vin)") (class "Default")
      (node (ref "C1p") (pin "1") (pinfunction "1_1") (pintype "passive"))
      (node (ref "C2p") (pin "2") (pinfunction "2_2") (pintype "passive"))
      (node (ref "C5p") (pin "1") (pinfunction "1_1") (pintype "passive"))
      (node (ref "C6p") (pin "1") (pinfunction "1_1") (pintype "passive"))
      (node (ref "DA1p") (pin "1") (pinfunction "Ctrl_1") (pintype "passive"))
      (node (ref "DA1p") (pin "3") (pinfunction "+Vin_3") (pintype "passive"))
      (node (ref "L1p") (pin "2") (pinfunction "2_2") (pintype "passive"))
      (node (ref "R1p") (pin "1") (pinfunction "1_1") (pintype "passive"))
    )
    (net (code "15") (name "Net-(DA1p--Vin)") (class "Default")
      (node (ref "C5p") (pin "2") (pinfunction "2_2") (pintype "passive"))
      (node (ref "C6p") (pin "2") (pinfunction "2_2") (pintype "passive"))
      (node (ref "C7p") (pin "1") (pinfunction "1_1") (pintype "passive"))
      (node (ref "C8p") (pin "1") (pinfunction "1_1") (pintype "passive"))
      (node (ref "DA1p") (pin "2") (pinfunction "-Vin_2") (pintype "passive"))
      (node (ref "L1p") (pin "4") (pinfunction "4_4") (pintype "passive"))
      (node (ref "VD2p") (pin "2") (pinfunction "2_2") (pintype "passive"))
    )
    (net (code "16") (name "Net-(DA2p-BST)") (class "Default")
      (node (ref "C14p") (pin "1") (pinfunction "1_1") (pintype "passive"))
      (node (ref "DA2p") (pin "8") (pinfunction "BST_8") (pintype "passive"))
    )
    (net (code "17") (name "Net-(DA2p-COMP)") (class "Default")
      (node (ref "DA2p") (pin "4") (pinfunction "COMP_4") (pintype "passive"))
      (node (ref "R7p") (pin "2") (pinfunction "2_2") (pintype "passive"))
    )
    (net (code "18") (name "Net-(DA2p-EN)") (class "Default")
      (node (ref "DA2p") (pin "7") (pinfunction "EN_7") (pintype "passive"))
      (node (ref "R3p") (pin "1") (pinfunction "1_1") (pintype "passive"))
    )
    (net (code "19") (name "Net-(DA2p-FB)") (class "Default")
      (node (ref "DA2p") (pin "6") (pinfunction "FB_6") (pintype "passive"))
      (node (ref "R5p") (pin "2") (pinfunction "2_2") (pintype "passive"))
      (node (ref "R9p") (pin "2") (pinfunction "2_2") (pintype "passive"))
    )
    (net (code "20") (name "Net-(DA2p-LX)") (class "Default")
      (node (ref "C14p") (pin "2") (pinfunction "2_2") (pintype "passive"))
      (node (ref "DA2p") (pin "2") (pinfunction "LX_2") (pintype "passive"))
      (node (ref "L2p") (pin "1") (pinfunction "1_1") (pintype "passive"))
    )
    (net (code "21") (name "Net-(DA2p-VCC)") (class "Default")
      (node (ref "C27p") (pin "1") (pinfunction "1_1") (pintype "passive"))
      (node (ref "DA2p") (pin "5") (pinfunction "VCC_5") (pintype "passive"))
    )
    (net (code "22") (name "Net-(DA3p-BST)") (class "Default")
      (node (ref "C9p") (pin "1") (pinfunction "1_1") (pintype "passive"))
      (node (ref "DA3p") (pin "8") (pinfunction "BST_8") (pintype "passive"))
    )
    (net (code "23") (name "Net-(DA3p-COMP)") (class "Default")
      (node (ref "DA3p") (pin "4") (pinfunction "COMP_4") (pintype "passive"))
      (node (ref "R8p") (pin "2") (pinfunction "2_2") (pintype "passive"))
    )
    (net (code "24") (name "Net-(DA3p-EN)") (class "Default")
      (node (ref "DA3p") (pin "7") (pinfunction "EN_7") (pintype "passive"))
      (node (ref "R4p") (pin "2") (pinfunction "2_2") (pintype "passive"))
    )
    (net (code "25") (name "Net-(DA3p-FB)") (class "Default")
      (node (ref "DA3p") (pin "6") (pinfunction "FB_6") (pintype "passive"))
      (node (ref "R10p") (pin "2") (pinfunction "2_2") (pintype "passive"))
      (node (ref "R6p") (pin "2") (pinfunction "2_2") (pintype "passive"))
    )
    (net (code "26") (name "Net-(DA3p-LX)") (class "Default")
      (node (ref "C9p") (pin "2") (pinfunction "2_2") (pintype "passive"))
      (node (ref "DA3p") (pin "2") (pinfunction "LX_2") (pintype "passive"))
      (node (ref "L3p") (pin "1") (pinfunction "1_1") (pintype "passive"))
    )
    (net (code "27") (name "Net-(DA3p-VCC)") (class "Default")
      (node (ref "C28p") (pin "1") (pinfunction "1_1") (pintype "passive"))
      (node (ref "DA3p") (pin "5") (pinfunction "VCC_5") (pintype "passive"))
    )
    (net (code "28") (name "Net-(DA4p-BST)") (class "Default")
      (node (ref "C32p") (pin "1") (pinfunction "1_1") (pintype "passive"))
      (node (ref "DA4p") (pin "8") (pinfunction "BST_8") (pintype "passive"))
    )
    (net (code "29") (name "Net-(DA4p-COMP)") (class "Default")
      (node (ref "DA4p") (pin "4") (pinfunction "COMP_4") (pintype "passive"))
      (node (ref "R14p") (pin "1") (pinfunction "1_1") (pintype "passive"))
    )
    (net (code "30") (name "Net-(DA4p-EN)") (class "Default")
      (node (ref "DA4p") (pin "7") (pinfunction "EN_7") (pintype "passive"))
      (node (ref "R11p") (pin "2") (pinfunction "2_2") (pintype "passive"))
    )
    (net (code "31") (name "Net-(DA4p-FB)") (class "Default")
      (node (ref "DA4p") (pin "6") (pinfunction "FB_6") (pintype "passive"))
      (node (ref "R12p") (pin "1") (pinfunction "1_1") (pintype "passive"))
      (node (ref "R15p") (pin "2") (pinfunction "2_2") (pintype "passive"))
    )
    (net (code "32") (name "Net-(DA4p-LX)") (class "Default")
      (node (ref "C32p") (pin "2") (pinfunction "2_2") (pintype "passive"))
      (node (ref "DA4p") (pin "2") (pinfunction "LX_2") (pintype "passive"))
      (node (ref "L4p") (pin "1") (pinfunction "1_1") (pintype "passive"))
    )
    (net (code "33") (name "Net-(DA4p-VCC)") (class "Default")
      (node (ref "C41p") (pin "1") (pinfunction "1_1") (pintype "passive"))
      (node (ref "DA4p") (pin "5") (pinfunction "VCC_5") (pintype "passive"))
    )
    (net (code "34") (name "Net-(R1p-Pad2)") (class "Default")
      (node (ref "R1p") (pin "2") (pinfunction "2_2") (pintype "passive"))
      (node (ref "VD2p") (pin "1") (pinfunction "1_1") (pintype "passive"))
    )
    (net (code "35") (name "Net-(VT1p-D)") (class "Default")
      (node (ref "FU1p") (pin "2") (pinfunction "2_2") (pintype "passive"))
      (node (ref "RU1p") (pin "2") (pinfunction "2_2") (pintype "passive"))
      (node (ref "VT1p") (pin "3") (pinfunction "D_3") (pintype "passive"))
    )
    (net (code "36") (name "Net-(VT1p-G)") (class "Default")
      (node (ref "R2p") (pin "2") (pinfunction "2_2") (pintype "passive"))
      (node (ref "VD1p") (pin "2") (pinfunction "2_2") (pintype "passive"))
      (node (ref "VT1p") (pin "1") (pinfunction "G_1") (pintype "passive"))
    )
    (net (code "37") (name "Net-(VT1p-S)") (class "Default")
      (node (ref "C4p") (pin "1") (pinfunction "1_1") (pintype "passive"))
      (node (ref "L1p") (pin "1") (pinfunction "1_1") (pintype "passive"))
      (node (ref "VD1p") (pin "1") (pinfunction "1_1") (pintype "passive"))
      (node (ref "VT1p") (pin "2") (pinfunction "S_2") (pintype "passive"))
    )
    (net (code "38") (name "PE") (class "Default")
      (node (ref "C2p") (pin "1") (pinfunction "1_1") (pintype "passive"))
      (node (ref "C8p") (pin "2") (pinfunction "2_2") (pintype "passive"))
    )
    (net (code "39") (name "unconnected-(DA1p-Trim-Pad6)") (class "Default")
      (node (ref "DA1p") (pin "6") (pinfunction "Trim_6") (pintype "passive+no_connect"))
    )
  )
)
